# DC_buck_converter_5V_OP.net
KiCad netlist of a schematic drawn in Altium Designer
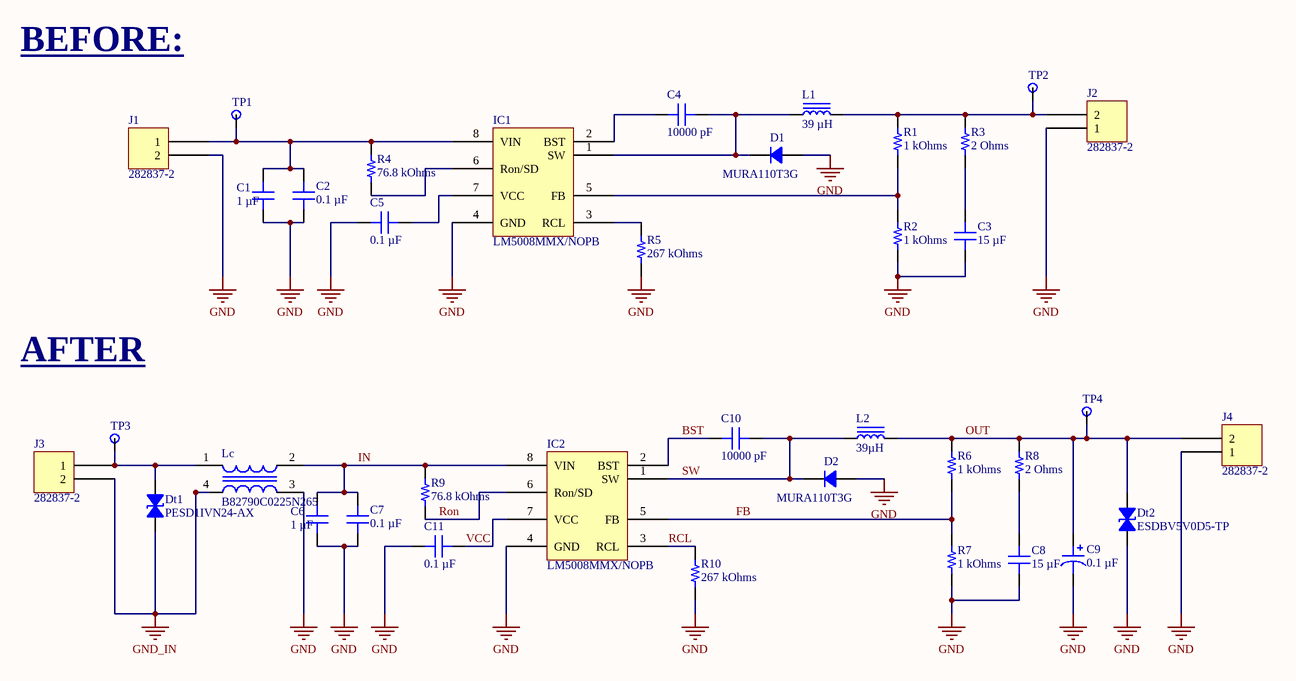
[diagram p0: DC_buck_converter_5V_OP..SchDoc]

(export (version "E")
  (design (tool "Eeschema 10.0.6"))
  (components
    (comp (ref "C1")
      (value "1 µF")
      (footprint "CAP 0603_1608")
      (description "CAP CER 1UF 50V X5R 0603")
      (fields (field (name "PART NUMBER") "UMK107ABJ105MAHT") (field (name "MANUFACTURER") "Taiyo Yuden"))
      (libsource (lib "Celestial Altium Library - altium_library") (part "Capacitor"))
    )
    (comp (ref "C2")
      (value "0.1 µF")
      (footprint "CAP 0603_1608")
      (description "CAP CER 0.1UF 50V X7R 0603")
      (fields (field (name "PART NUMBER") "C0603C104K5RAC7411") (field (name "MANUFACTURER") "KEMET"))
      (libsource (lib "Celestial Altium Library - altium_library") (part "Capacitor"))
    )
    (comp (ref "C3")
      (value "15 µF")
      (footprint "CAP 0603_1608")
      (description "CAP CER 15UF 6.3V X5R 0603")
      (fields
        (field (name "PART NUMBER") "C1608X5R0J156M080AC")
        (field (name "MANUFACTURER") "TDK Corporation")
      )
      (libsource (lib "Celestial Altium Library - altium_library") (part "Capacitor"))
    )
    (comp (ref "C4")
      (value "10000 pF")
      (footprint "CAP 0603_1608")
      (description "CAP CER 10000PF 100V X7R 0603")
      (fields (field (name "PART NUMBER") "AC0603KRX7R0BB103") (field (name "MANUFACTURER") "Yageo"))
      (libsource (lib "Celestial Altium Library - altium_library") (part "Capacitor"))
    )
    (comp (ref "C5")
      (value "0.1 µF")
      (footprint "CAP 0603_1608")
      (description "CAP CER 0.1UF 50V X7R 0603")
      (fields (field (name "PART NUMBER") "C0603C104K5RAC7411") (field (name "MANUFACTURER") "KEMET"))
      (libsource (lib "Celestial Altium Library - altium_library") (part "Capacitor"))
    )
    (comp (ref "C6")
      (value "1 µF")
      (footprint "CAP 0603_1608")
      (description "CAP CER 1UF 50V X5R 0603")
      (fields (field (name "PART NUMBER") "UMK107ABJ105MAHT") (field (name "MANUFACTURER") "Taiyo Yuden"))
      (libsource (lib "Celestial Altium Library - altium_library") (part "Capacitor"))
    )
    (comp (ref "C7")
      (value "0.1 µF")
      (footprint "CAP 0603_1608")
      (description "CAP CER 0.1UF 50V X7R 0603")
      (fields (field (name "PART NUMBER") "C0603C104K5RAC7411") (field (name "MANUFACTURER") "KEMET"))
      (libsource (lib "Celestial Altium Library - altium_library") (part "Capacitor"))
    )
    (comp (ref "C8")
      (value "15 µF")
      (footprint "CAP 0603_1608")
      (description "CAP CER 15UF 10V X5R 0603")
      (fields
        (field (name "PART NUMBER") "C1608X5R1A156M080AC")
        (field (name "MANUFACTURER") "TDK Corporation")
      )
      (libsource (lib "Celestial Altium Library - altium_library") (part "Capacitor"))
    )
    (comp (ref "C9")
      (value "0.1 µF")
      (footprint "CAP POL 1206_3216")
      (description "CAP TANT 0.1UF 10% 35V 1206")
      (fields (field (name "PART NUMBER") "T494A104K035AT") (field (name "MANUFACTURER") "KEMET"))
      (libsource (lib "Celestial Altium Library - altium_library") (part "Polarised Capacitor"))
    )
    (comp (ref "C10")
      (value "10000 pF")
      (footprint "CAP 0603_1608")
      (description "CAP CER 10000PF 100V X7R 0603")
      (fields (field (name "PART NUMBER") "AC0603KRX7R0BB103") (field (name "MANUFACTURER") "Yageo"))
      (libsource (lib "Celestial Altium Library - altium_library") (part "Capacitor"))
    )
    (comp (ref "C11")
      (value "0.1 µF")
      (footprint "CAP 0603_1608")
      (description "CAP CER 0.1UF 50V X7R 0603")
      (fields (field (name "PART NUMBER") "C0603C104K5RAC7411") (field (name "MANUFACTURER") "KEMET"))
      (libsource (lib "Celestial Altium Library - altium_library") (part "Capacitor"))
    )
    (comp (ref "D1")
      (value "MURA110T3G")
      (footprint "DO214AC SMA")
      (description "DIODE GEN PURP 100V 2A SMA")
      (fields (field (name "MANUFACTURER") "ON Semiconductor"))
      (libsource (lib "Celestial Altium Library - altium_library") (part "Diode"))
    )
    (comp (ref "D2")
      (value "MURA110T3G")
      (footprint "DO214AC SMA")
      (description "DIODE GEN PURP 100V 2A SMA")
      (fields (field (name "MANUFACTURER") "ON Semiconductor"))
      (libsource (lib "Celestial Altium Library - altium_library") (part "Diode"))
    )
    (comp (ref "Dt1")
      (value "PESD1IVN24-AX")
      (footprint "SOD323")
      (description "TVS DIODE 24VWM 42VC SOD323")
      (fields (field (name "MANUFACTURER") "Nexperia USA Inc."))
      (libsource (lib "Celestial Altium Library - altium_library") (part "Diode TVS"))
    )
    (comp (ref "Dt2")
      (value "ESDBV5V0D5-TP")
      (footprint "SOD523F")
      (description "TVS DIODE 5VWM 13VC SOD523")
      (fields (field (name "MANUFACTURER") "Micro Commercial Co"))
      (libsource (lib "Celestial Altium Library - altium_library") (part "Diode TVS"))
    )
    (comp (ref "IC1")
      (value "LM5008MMX/NOPB")
      (footprint "TI VSSOP-8 DGK")
      (description "IC REG BUCK ADJ 350MA 8VSSOP")
      (fields (field (name "MANUFACTURER") "Texas Instruments"))
      (libsource (lib "Celestial Altium Library - altium_library") (part "TI LM5008"))
    )
    (comp (ref "IC2")
      (value "LM5008MMX/NOPB")
      (footprint "TI VSSOP-8 DGK")
      (description "IC REG BUCK ADJ 350MA 8VSSOP")
      (fields (field (name "MANUFACTURER") "Texas Instruments"))
      (libsource (lib "Celestial Altium Library - altium_library") (part "TI LM5008"))
    )
    (comp (ref "J1")
      (value "282837-2")
      (footprint "TE 282837-2")
      (description "TERM BLK 2P SIDE ENT 5.08MM PCB")
      (fields (field (name "MANUFACTURER") "TE Connectivity AMP Connectors") (field (name "VOLTAGE") "300 V"))
      (libsource (lib "Celestial Altium Library - altium_library") (part "2 Pin"))
    )
    (comp (ref "J2")
      (value "282837-2")
      (footprint "TE 282837-2")
      (description "TERM BLK 2P SIDE ENT 5.08MM PCB")
      (fields (field (name "MANUFACTURER") "TE Connectivity AMP Connectors") (field (name "VOLTAGE") "300 V"))
      (libsource (lib "") (part "2 Pin_1"))
    )
    (comp (ref "J3")
      (value "282837-2")
      (footprint "TE 282837-2")
      (description "TERM BLK 2P SIDE ENT 5.08MM PCB")
      (fields (field (name "MANUFACTURER") "TE Connectivity AMP Connectors") (field (name "VOLTAGE") "300 V"))
      (libsource (lib "Celestial Altium Library - altium_library") (part "2 Pin"))
    )
    (comp (ref "J4")
      (value "282837-2")
      (footprint "TE 282837-2")
      (description "TERM BLK 2P SIDE ENT 5.08MM PCB")
      (fields (field (name "MANUFACTURER") "TE Connectivity AMP Connectors") (field (name "VOLTAGE") "300 V"))
      (libsource (lib "") (part "2 Pin_1"))
    )
    (comp (ref "L1")
      (value "39 µH")
      (footprint "BOURNS SRR1280")
      (description "FIXED IND 39UH 3.2A 70 MOHM SMD")
      (fields (field (name "PART NUMBER") "SRR1280-390M") (field (name "MANUFACTURER") "Bourns Inc."))
      (libsource (lib "Celestial Altium Library - altium_library") (part "Inductor"))
    )
    (comp (ref "L2")
      (value "39µH")
      (footprint "BOURNS SRR6028")
      (description "FIXED IND 39UH 1A 195 MOHM SMD")
      (fields (field (name "PART NUMBER") "SRR6028-390Y") (field (name "MANUFACTURER") "Bourns Inc."))
      (libsource (lib "Celestial Altium Library - altium_library") (part "Inductor"))
    )
    (comp (ref "Lc")
      (value "B82790C0225N265")
      (footprint "FL_B82790C0225N265")
      (description "Common Mode Filter / Choke, 0.005 - 4.7 mH, 200 - 1000 mA")
      (fields (field (name "MF") "EPCOS"))
      (libsource (lib "B82790C0225N265") (part "B82790C0225N265"))
    )
    (comp (ref "R1")
      (value "1 kOhms")
      (footprint "RES 0603_1608")
      (description "RES SMD 1K OHM 0.5% 1/10W 0603")
      (fields (field (name "PART NUMBER") "AT0603DRD071KL") (field (name "MANUFACTURER") "Yageo"))
      (libsource (lib "Celestial Altium Library - altium_library") (part "Resistor"))
    )
    (comp (ref "R2")
      (value "1 kOhms")
      (footprint "RES 0603_1608")
      (description "RES SMD 1K OHM 0.5% 1/10W 0603")
      (fields (field (name "PART NUMBER") "AT0603DRD071KL") (field (name "MANUFACTURER") "Yageo"))
      (libsource (lib "Celestial Altium Library - altium_library") (part "Resistor"))
    )
    (comp (ref "R3")
      (value "2 Ohms")
      (footprint "RES 0603_1608")
      (description "SULFUR TOLERANT CHIP RESISTORS")
      (fields (field (name "PART NUMBER") "SFR03EZPJ2R0") (field (name "MANUFACTURER") "Rohm Semiconductor"))
      (libsource (lib "Celestial Altium Library - altium_library") (part "Resistor"))
    )
    (comp (ref "R4")
      (value "76.8 kOhms")
      (footprint "RES 0603_1608")
      (description "RES SMD 76.8KOHM 0.1% 1/10W 0603")
      (fields (field (name "PART NUMBER") "RG1608P-7682-B-T5") (field (name "MANUFACTURER") "Susumu"))
      (libsource (lib "Celestial Altium Library - altium_library") (part "Resistor"))
    )
    (comp (ref "R5")
      (value "267 kOhms")
      (footprint "RES 0603_1608")
      (description "RES SMD 267K OHM 0.1% 1/10W 0603")
      (fields (field (name "PART NUMBER") "RT0603BRD07267KL") (field (name "MANUFACTURER") "Yageo"))
      (libsource (lib "Celestial Altium Library - altium_library") (part "Resistor"))
    )
    (comp (ref "R6")
      (value "1 kOhms")
      (footprint "RES 0603_1608")
      (description "RES SMD 1K OHM 0.5% 1/10W 0603")
      (fields (field (name "PART NUMBER") "AT0603DRD071KL") (field (name "MANUFACTURER") "Yageo"))
      (libsource (lib "Celestial Altium Library - altium_library") (part "Resistor"))
    )
    (comp (ref "R7")
      (value "1 kOhms")
      (footprint "RES 0603_1608")
      (description "RES SMD 1K OHM 0.5% 1/10W 0603")
      (fields (field (name "PART NUMBER") "AT0603DRD071KL") (field (name "MANUFACTURER") "Yageo"))
      (libsource (lib "Celestial Altium Library - altium_library") (part "Resistor"))
    )
    (comp (ref "R8")
      (value "2 Ohms")
      (footprint "RES 0603_1608")
      (description "SULFUR TOLERANT CHIP RESISTORS")
      (fields (field (name "PART NUMBER") "SFR03EZPJ2R0") (field (name "MANUFACTURER") "Rohm Semiconductor"))
      (libsource (lib "Celestial Altium Library - altium_library") (part "Resistor"))
    )
    (comp (ref "R9")
      (value "76.8 kOhms")
      (footprint "RES 0603_1608")
      (description "RES SMD 76.8KOHM 0.1% 1/10W 0603")
      (fields (field (name "PART NUMBER") "RG1608P-7682-B-T5") (field (name "MANUFACTURER") "Susumu"))
      (libsource (lib "Celestial Altium Library - altium_library") (part "Resistor"))
    )
    (comp (ref "R10")
      (value "267 kOhms")
      (footprint "RES 0603_1608")
      (description "RES SMD 267K OHM 0.1% 1/10W 0603")
      (fields (field (name "PART NUMBER") "RT0603BRD07267KL") (field (name "MANUFACTURER") "Yageo"))
      (libsource (lib "Celestial Altium Library - altium_library") (part "Resistor"))
    )
    (comp (ref "TP1") (value "TP_1") (footprint "Testpoint") (libsource (lib "Schlib1") (part "Testpoint")))
    (comp (ref "TP2") (value "TP_1") (footprint "Testpoint") (libsource (lib "Schlib1") (part "Testpoint")))
    (comp (ref "TP3") (value "TP_1") (footprint "Testpoint") (libsource (lib "Schlib1") (part "Testpoint")))
    (comp (ref "TP4") (value "TP_1") (footprint "Testpoint") (libsource (lib "Schlib1") (part "Testpoint")))
  )
  (nets
    (net (code "1") (name "/BST") (class "Default")
      (node (ref "C10") (pin "1") (pinfunction "1_1") (pintype "passive"))
      (node (ref "IC2") (pin "2") (pinfunction "BST_2") (pintype "passive"))
    )
    (net (code "2") (name "/FB") (class "Default")
      (node (ref "IC2") (pin "5") (pinfunction "FB_5") (pintype "passive"))
      (node (ref "R6") (pin "1") (pinfunction "1_1") (pintype "passive"))
      (node (ref "R7") (pin "2") (pinfunction "2_2") (pintype "passive"))
    )
    (net (code "3") (name "/IN") (class "Default")
      (node (ref "C6") (pin "2") (pinfunction "2_2") (pintype "passive"))
      (node (ref "C7") (pin "2") (pinfunction "2_2") (pintype "passive"))
      (node (ref "IC2") (pin "8") (pinfunction "VIN_8") (pintype "passive"))
      (node (ref "Lc") (pin "2") (pinfunction "2_2") (pintype "passive"))
      (node (ref "R9") (pin "2") (pinfunction "2_2") (pintype "passive"))
    )
    (net (code "4") (name "/OUT") (class "Default")
      (node (ref "C9") (pin "1") (pinfunction "1_1") (pintype "passive"))
      (node (ref "Dt2") (pin "2") (pinfunction "2_2") (pintype "passive"))
      (node (ref "J4") (pin "2") (pinfunction "2_2") (pintype "passive"))
      (node (ref "L2") (pin "2") (pinfunction "2_2") (pintype "passive"))
      (node (ref "R6") (pin "2") (pinfunction "2_2") (pintype "passive"))
      (node (ref "R8") (pin "2") (pinfunction "2_2") (pintype "passive"))
    )
    (net (code "5") (name "/RCL") (class "Default")
      (node (ref "IC2") (pin "3") (pinfunction "RCL_3") (pintype "passive"))
      (node (ref "R10") (pin "2") (pinfunction "2_2") (pintype "passive"))
    )
    (net (code "6") (name "/Ron") (class "Default")
      (node (ref "IC2") (pin "6") (pinfunction "Ron/SD_6") (pintype "passive"))
      (node (ref "R9") (pin "1") (pinfunction "1_1") (pintype "passive"))
    )
    (net (code "7") (name "/SW") (class "Default")
      (node (ref "C10") (pin "2") (pinfunction "2_2") (pintype "passive"))
      (node (ref "D2") (pin "2") (pinfunction "2_2") (pintype "passive"))
      (node (ref "IC2") (pin "1") (pinfunction "SW_1") (pintype "passive"))
      (node (ref "L2") (pin "1") (pinfunction "1_1") (pintype "passive"))
    )
    (net (code "8") (name "/VCC") (class "Default")
      (node (ref "C11") (pin "1") (pinfunction "1_1") (pintype "passive"))
      (node (ref "IC2") (pin "7") (pinfunction "VCC_7") (pintype "passive"))
    )
    (net (code "9") (name "GND") (class "Default")
      (node (ref "C1") (pin "1") (pinfunction "1_1") (pintype "passive"))
      (node (ref "C11") (pin "2") (pinfunction "2_2") (pintype "passive"))
      (node (ref "C2") (pin "1") (pinfunction "1_1") (pintype "passive"))
      (node (ref "C3") (pin "1") (pinfunction "1_1") (pintype "passive"))
      (node (ref "C5") (pin "2") (pinfunction "2_2") (pintype "passive"))
      (node (ref "C6") (pin "1") (pinfunction "1_1") (pintype "passive"))
      (node (ref "C7") (pin "1") (pinfunction "1_1") (pintype "passive"))
      (node (ref "C8") (pin "1") (pinfunction "1_1") (pintype "passive"))
      (node (ref "C9") (pin "2") (pinfunction "2_2") (pintype "passive"))
      (node (ref "D1") (pin "1") (pinfunction "1_1") (pintype "passive"))
      (node (ref "D2") (pin "1") (pinfunction "1_1") (pintype "passive"))
      (node (ref "Dt2") (pin "1") (pinfunction "1_1") (pintype "passive"))
      (node (ref "IC1") (pin "4") (pinfunction "GND_4") (pintype "passive"))
      (node (ref "IC2") (pin "4") (pinfunction "GND_4") (pintype "passive"))
      (node (ref "J1") (pin "2") (pinfunction "2_2") (pintype "passive"))
      (node (ref "J2") (pin "1") (pinfunction "1_1") (pintype "passive"))
      (node (ref "J4") (pin "1") (pinfunction "1_1") (pintype "passive"))
      (node (ref "Lc") (pin "3") (pinfunction "3_3") (pintype "passive"))
      (node (ref "R10") (pin "1") (pinfunction "1_1") (pintype "passive"))
      (node (ref "R2") (pin "1") (pinfunction "1_1") (pintype "passive"))
      (node (ref "R5") (pin "1") (pinfunction "1_1") (pintype "passive"))
      (node (ref "R7") (pin "1") (pinfunction "1_1") (pintype "passive"))
    )
    (net (code "10") (name "GND_IN") (class "Default")
      (node (ref "Dt1") (pin "1") (pinfunction "1_1") (pintype "passive"))
      (node (ref "J3") (pin "2") (pinfunction "2_2") (pintype "passive"))
      (node (ref "Lc") (pin "4") (pinfunction "4_4") (pintype "passive"))
    )
    (net (code "11") (name "Net-(C3-Pad2)") (class "Default")
      (node (ref "C3") (pin "2") (pinfunction "2_2") (pintype "passive"))
      (node (ref "R3") (pin "1") (pinfunction "1_1") (pintype "passive"))
    )
    (net (code "12") (name "Net-(C8-Pad2)") (class "Default")
      (node (ref "C8") (pin "2") (pinfunction "2_2") (pintype "passive"))
      (node (ref "R8") (pin "1") (pinfunction "1_1") (pintype "passive"))
    )
    (net (code "13") (name "Net-(Dt1-Pad2)") (class "Default")
      (node (ref "Dt1") (pin "2") (pinfunction "2_2") (pintype "passive"))
      (node (ref "J3") (pin "1") (pinfunction "1_1") (pintype "passive"))
      (node (ref "Lc") (pin "1") (pinfunction "1_1") (pintype "passive"))
    )
    (net (code "14") (name "Net-(IC1-BST)") (class "Default")
      (node (ref "C4") (pin "1") (pinfunction "1_1") (pintype "passive"))
      (node (ref "IC1") (pin "2") (pinfunction "BST_2") (pintype "passive"))
    )
    (net (code "15") (name "Net-(IC1-FB)") (class "Default")
      (node (ref "IC1") (pin "5") (pinfunction "FB_5") (pintype "passive"))
      (node (ref "R1") (pin "1") (pinfunction "1_1") (pintype "passive"))
      (node (ref "R2") (pin "2") (pinfunction "2_2") (pintype "passive"))
    )
    (net (code "16") (name "Net-(IC1-RCL)") (class "Default")
      (node (ref "IC1") (pin "3") (pinfunction "RCL_3") (pintype "passive"))
      (node (ref "R5") (pin "2") (pinfunction "2_2") (pintype "passive"))
    )
    (net (code "17") (name "Net-(IC1-Ron{slash}SD)") (class "Default")
      (node (ref "IC1") (pin "6") (pinfunction "Ron/SD_6") (pintype "passive"))
      (node (ref "R4") (pin "1") (pinfunction "1_1") (pintype "passive"))
    )
    (net (code "18") (name "Net-(IC1-SW)") (class "Default")
      (node (ref "C4") (pin "2") (pinfunction "2_2") (pintype "passive"))
      (node (ref "D1") (pin "2") (pinfunction "2_2") (pintype "passive"))
      (node (ref "IC1") (pin "1") (pinfunction "SW_1") (pintype "passive"))
      (node (ref "L1") (pin "1") (pinfunction "1_1") (pintype "passive"))
    )
    (net (code "19") (name "Net-(IC1-VCC)") (class "Default")
      (node (ref "C5") (pin "1") (pinfunction "1_1") (pintype "passive"))
      (node (ref "IC1") (pin "7") (pinfunction "VCC_7") (pintype "passive"))
    )
    (net (code "20") (name "Net-(IC1-VIN)") (class "Default")
      (node (ref "C1") (pin "2") (pinfunction "2_2") (pintype "passive"))
      (node (ref "C2") (pin "2") (pinfunction "2_2") (pintype "passive"))
      (node (ref "IC1") (pin "8") (pinfunction "VIN_8") (pintype "passive"))
      (node (ref "J1") (pin "1") (pinfunction "1_1") (pintype "passive"))
      (node (ref "R4") (pin "2") (pinfunction "2_2") (pintype "passive"))
    )
    (net (code "21") (name "Net-(J2-Pad2)") (class "Default")
      (node (ref "J2") (pin "2") (pinfunction "2_2") (pintype "passive"))
      (node (ref "L1") (pin "2") (pinfunction "2_2") (pintype "passive"))
      (node (ref "R1") (pin "2") (pinfunction "2_2") (pintype "passive"))
      (node (ref "R3") (pin "2") (pinfunction "2_2") (pintype "passive"))
    )
  )
)
